# LED-Reorg-SMD.net
KiCad netlist of a schematic drawn in EAGLE
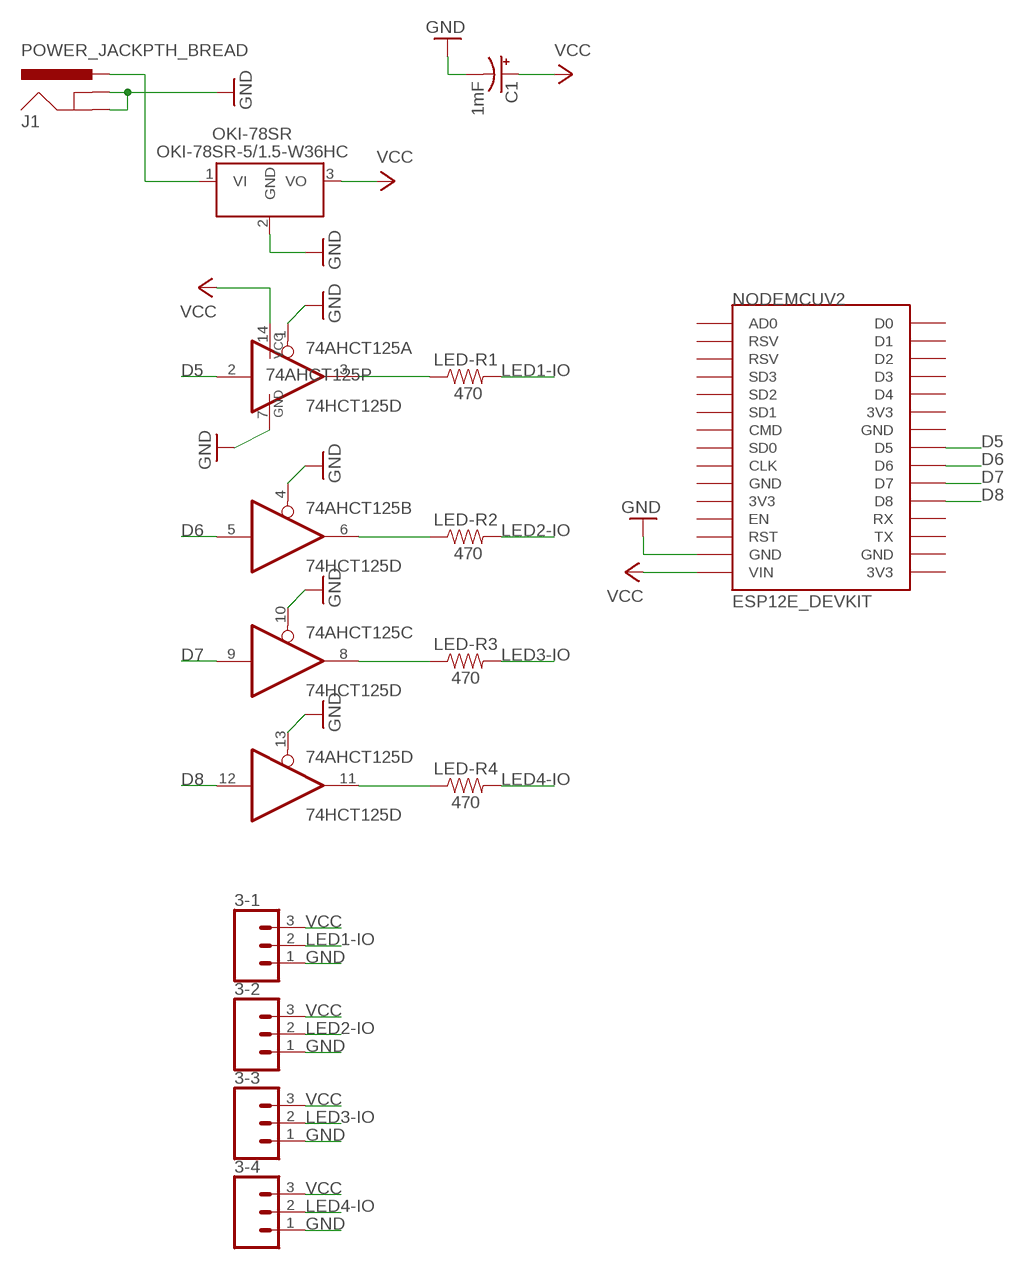
[diagram p0: schematic, sheet 1]

(export (version "E")
  (design (tool "Eeschema 10.0.6"))
  (components
    (comp (ref "3-1")
      (value "CONN_03SCREW")
      (footprint "eagle-import:SCREWTERMINAL-3.5MM-3")
      (libsource (lib "eagle-import") (part "CONN_03SCREW"))
    )
    (comp (ref "3-2")
      (value "CONN_03SCREW")
      (footprint "eagle-import:SCREWTERMINAL-3.5MM-3")
      (libsource (lib "eagle-import") (part "CONN_03SCREW"))
    )
    (comp (ref "3-3")
      (value "CONN_03SCREW")
      (footprint "eagle-import:SCREWTERMINAL-3.5MM-3")
      (libsource (lib "eagle-import") (part "CONN_03SCREW"))
    )
    (comp (ref "3-4")
      (value "CONN_03SCREW")
      (footprint "eagle-import:SCREWTERMINAL-3.5MM-3")
      (libsource (lib "eagle-import") (part "CONN_03SCREW"))
    )
    (comp (ref "74AHCT125")
      (value "74HCT125D")
      (footprint "eagle-import:SO14")
      (libsource (lib "eagle-import") (part "74125DHCT"))
    )
    (comp (ref "C1")
      (value "1mF")
      (footprint "eagle-import:CPOL-RADIAL-5MM-10MM")
      (libsource (lib "eagle-import") (part "1000UF-RADIAL-5MM-25V-20%"))
    )
    (comp (ref "J1")
      (value "POWER_JACKPTH_BREAD")
      (footprint "eagle-import:POWER_JACK_PTH_BREAD")
      (libsource (lib "eagle-import") (part "POWER_JACKPTH_BREAD"))
    )
    (comp (ref "LED-R1")
      (value "470")
      (footprint "eagle-import:1206")
      (libsource (lib "eagle-import") (part "RESISTOR1206"))
    )
    (comp (ref "LED-R2")
      (value "470")
      (footprint "eagle-import:1206")
      (libsource (lib "eagle-import") (part "RESISTOR1206"))
    )
    (comp (ref "LED-R3")
      (value "470")
      (footprint "eagle-import:1206")
      (libsource (lib "eagle-import") (part "RESISTOR1206"))
    )
    (comp (ref "LED-R4")
      (value "470")
      (footprint "eagle-import:1206")
      (libsource (lib "eagle-import") (part "RESISTOR1206"))
    )
    (comp (ref "NODEMCUV2")
      (value "ESP12E_DEVKIT")
      (footprint "eagle-import:ESP12E_DEVKIT")
      (libsource (lib "eagle-import") (part "ESP12E_DEVKIT"))
    )
    (comp (ref "OKI-78SR")
      (value "OKI-78SR-5/1.5-W36HC")
      (footprint "eagle-import:OKI-78SR_HORIZ")
      (libsource (lib "eagle-import") (part "OKI-78SR-/1.5-W36?CH5"))
    )
  )
  (nets
    (net (code "1") (name "/D5") (class "Default")
      (node (ref "74AHCT125") (pin "2") (pinfunction "I_2") (pintype "input"))
      (node (ref "NODEMCUV2") (pin "D5") (pinfunction "D5_D5") (pintype "bidirectional"))
    )
    (net (code "2") (name "/D6") (class "Default")
      (node (ref "74AHCT125") (pin "5") (pinfunction "I_5") (pintype "input"))
      (node (ref "NODEMCUV2") (pin "D6") (pinfunction "D6_D6") (pintype "bidirectional"))
    )
    (net (code "3") (name "/D7") (class "Default")
      (node (ref "74AHCT125") (pin "9") (pinfunction "I_9") (pintype "input"))
      (node (ref "NODEMCUV2") (pin "D7") (pinfunction "D7_D7") (pintype "bidirectional"))
    )
    (net (code "4") (name "/D8") (class "Default")
      (node (ref "74AHCT125") (pin "12") (pinfunction "I_12") (pintype "input"))
      (node (ref "NODEMCUV2") (pin "D8") (pinfunction "D8_D8") (pintype "bidirectional"))
    )
    (net (code "5") (name "/LED1-IO") (class "Default")
      (node (ref "3-1") (pin "2") (pinfunction "2_2") (pintype "passive"))
      (node (ref "LED-R1") (pin "2") (pinfunction "2_2") (pintype "passive"))
    )
    (net (code "6") (name "/LED2-IO") (class "Default")
      (node (ref "3-2") (pin "2") (pinfunction "2_2") (pintype "passive"))
      (node (ref "LED-R2") (pin "2") (pinfunction "2_2") (pintype "passive"))
    )
    (net (code "7") (name "/LED3-IO") (class "Default")
      (node (ref "3-3") (pin "2") (pinfunction "2_2") (pintype "passive"))
      (node (ref "LED-R3") (pin "2") (pinfunction "2_2") (pintype "passive"))
    )
    (net (code "8") (name "/LED4-IO") (class "Default")
      (node (ref "3-4") (pin "2") (pinfunction "2_2") (pintype "passive"))
      (node (ref "LED-R4") (pin "2") (pinfunction "2_2") (pintype "passive"))
    )
    (net (code "9") (name "GND") (class "Default")
      (node (ref "3-1") (pin "1") (pinfunction "1_1") (pintype "passive"))
      (node (ref "3-2") (pin "1") (pinfunction "1_1") (pintype "passive"))
      (node (ref "3-3") (pin "1") (pinfunction "1_1") (pintype "passive"))
      (node (ref "3-4") (pin "1") (pinfunction "1_1") (pintype "passive"))
      (node (ref "74AHCT125") (pin "1") (pinfunction "OE_1") (pintype "input"))
      (node (ref "74AHCT125") (pin "10") (pinfunction "OE_10") (pintype "input"))
      (node (ref "74AHCT125") (pin "13") (pinfunction "OE_13") (pintype "input"))
      (node (ref "74AHCT125") (pin "4") (pinfunction "OE_4") (pintype "input"))
      (node (ref "74AHCT125") (pin "7") (pinfunction "GND_7") (pintype "power_in"))
      (node (ref "C1") (pin "-") (pinfunction "-_-") (pintype "passive"))
      (node (ref "J1") (pin "GND") (pinfunction "GND_GND") (pintype "bidirectional"))
      (node (ref "J1") (pin "GNDBREAK") (pinfunction "GNDBREAK_GNDBREAK") (pintype "bidirectional"))
      (node (ref "NODEMCUV2") (pin "GND@1") (pinfunction "GND_GND@1") (pintype "bidirectional"))
      (node (ref "OKI-78SR") (pin "2") (pinfunction "GND_2") (pintype "bidirectional"))
    )
    (net (code "10") (name "Net-(74AHCT125A-O)") (class "Default")
      (node (ref "74AHCT125") (pin "3") (pinfunction "O_3") (pintype "tri_state"))
      (node (ref "LED-R1") (pin "1") (pinfunction "1_1") (pintype "passive"))
    )
    (net (code "11") (name "Net-(74AHCT125B-O)") (class "Default")
      (node (ref "74AHCT125") (pin "6") (pinfunction "O_6") (pintype "tri_state"))
      (node (ref "LED-R2") (pin "1") (pinfunction "1_1") (pintype "passive"))
    )
    (net (code "12") (name "Net-(74AHCT125C-O)") (class "Default")
      (node (ref "74AHCT125") (pin "8") (pinfunction "O_8") (pintype "tri_state"))
      (node (ref "LED-R3") (pin "1") (pinfunction "1_1") (pintype "passive"))
    )
    (net (code "13") (name "Net-(74AHCT125D-O)") (class "Default")
      (node (ref "74AHCT125") (pin "11") (pinfunction "O_11") (pintype "tri_state"))
      (node (ref "LED-R4") (pin "1") (pinfunction "1_1") (pintype "passive"))
    )
    (net (code "14") (name "Net-(OKI-78SR-VI)") (class "Default")
      (node (ref "J1") (pin "PWR") (pinfunction "PWR_PWR") (pintype "bidirectional"))
      (node (ref "OKI-78SR") (pin "1") (pinfunction "VI_1") (pintype "bidirectional"))
    )
    (net (code "15") (name "VCC") (class "Default")
      (node (ref "3-1") (pin "3") (pinfunction "3_3") (pintype "passive"))
      (node (ref "3-2") (pin "3") (pinfunction "3_3") (pintype "passive"))
      (node (ref "3-3") (pin "3") (pinfunction "3_3") (pintype "passive"))
      (node (ref "3-4") (pin "3") (pinfunction "3_3") (pintype "passive"))
      (node (ref "74AHCT125") (pin "14") (pinfunction "VCC_14") (pintype "power_in"))
      (node (ref "C1") (pin "+") (pinfunction "+_+") (pintype "passive"))
      (node (ref "NODEMCUV2") (pin "VIN") (pinfunction "VIN_VIN") (pintype "bidirectional"))
      (node (ref "OKI-78SR") (pin "3") (pinfunction "VO_3") (pintype "bidirectional"))
    )
    (net (code "16") (name "unconnected-(NODEMCUV2-3V3-Pad3V3@0)") (class "Default")
      (node (ref "NODEMCUV2") (pin "3V3@0") (pinfunction "3V3_3V3@0") (pintype "bidirectional"))
    )
    (net (code "17") (name "unconnected-(NODEMCUV2-3V3-Pad3V3@1)") (class "Default")
      (node (ref "NODEMCUV2") (pin "3V3@1") (pinfunction "3V3_3V3@1") (pintype "bidirectional"))
    )
    (net (code "18") (name "unconnected-(NODEMCUV2-3V3-Pad3V3@2)") (class "Default")
      (node (ref "NODEMCUV2") (pin "3V3@2") (pinfunction "3V3_3V3@2") (pintype "bidirectional"))
    )
    (net (code "19") (name "unconnected-(NODEMCUV2-GND-PadGND@0)") (class "Default")
      (node (ref "NODEMCUV2") (pin "GND@0") (pinfunction "GND_GND@0") (pintype "bidirectional"))
    )
    (net (code "20") (name "unconnected-(NODEMCUV2-GND-PadGND@2)") (class "Default")
      (node (ref "NODEMCUV2") (pin "GND@2") (pinfunction "GND_GND@2") (pintype "bidirectional"))
    )
    (net (code "21") (name "unconnected-(NODEMCUV2-GND-PadGND@3)") (class "Default")
      (node (ref "NODEMCUV2") (pin "GND@3") (pinfunction "GND_GND@3") (pintype "bidirectional"))
    )
    (net (code "22") (name "unconnected-(NODEMCUV2-PadAD0)") (class "Default")
      (node (ref "NODEMCUV2") (pin "AD0") (pinfunction "AD0_AD0") (pintype "bidirectional"))
    )
    (net (code "23") (name "unconnected-(NODEMCUV2-PadCLK)") (class "Default")
      (node (ref "NODEMCUV2") (pin "CLK") (pinfunction "CLK_CLK") (pintype "bidirectional"))
    )
    (net (code "24") (name "unconnected-(NODEMCUV2-PadCMD)") (class "Default")
      (node (ref "NODEMCUV2") (pin "CMD") (pinfunction "CMD_CMD") (pintype "bidirectional"))
    )
    (net (code "25") (name "unconnected-(NODEMCUV2-PadD0)") (class "Default")
      (node (ref "NODEMCUV2") (pin "D0") (pinfunction "D0_D0") (pintype "bidirectional"))
    )
    (net (code "26") (name "unconnected-(NODEMCUV2-PadD1)") (class "Default")
      (node (ref "NODEMCUV2") (pin "D1") (pinfunction "D1_D1") (pintype "bidirectional"))
    )
    (net (code "27") (name "unconnected-(NODEMCUV2-PadD2)") (class "Default")
      (node (ref "NODEMCUV2") (pin "D2") (pinfunction "D2_D2") (pintype "bidirectional"))
    )
    (net (code "28") (name "unconnected-(NODEMCUV2-PadD3)") (class "Default")
      (node (ref "NODEMCUV2") (pin "D3") (pinfunction "D3_D3") (pintype "bidirectional"))
    )
    (net (code "29") (name "unconnected-(NODEMCUV2-PadD4)") (class "Default")
      (node (ref "NODEMCUV2") (pin "D4") (pinfunction "D4_D4") (pintype "bidirectional"))
    )
    (net (code "30") (name "unconnected-(NODEMCUV2-PadEN)") (class "Default")
      (node (ref "NODEMCUV2") (pin "EN") (pinfunction "EN_EN") (pintype "bidirectional"))
    )
    (net (code "31") (name "unconnected-(NODEMCUV2-PadRST)") (class "Default")
      (node (ref "NODEMCUV2") (pin "RST") (pinfunction "RST_RST") (pintype "bidirectional"))
    )
    (net (code "32") (name "unconnected-(NODEMCUV2-PadRX)") (class "Default")
      (node (ref "NODEMCUV2") (pin "RX") (pinfunction "RX_RX") (pintype "bidirectional"))
    )
    (net (code "33") (name "unconnected-(NODEMCUV2-PadSD0)") (class "Default")
      (node (ref "NODEMCUV2") (pin "SD0") (pinfunction "SD0_SD0") (pintype "bidirectional"))
    )
    (net (code "34") (name "unconnected-(NODEMCUV2-PadSD1)") (class "Default")
      (node (ref "NODEMCUV2") (pin "SD1") (pinfunction "SD1_SD1") (pintype "bidirectional"))
    )
    (net (code "35") (name "unconnected-(NODEMCUV2-PadSD2)") (class "Default")
      (node (ref "NODEMCUV2") (pin "SD2") (pinfunction "SD2_SD2") (pintype "bidirectional"))
    )
    (net (code "36") (name "unconnected-(NODEMCUV2-PadSD3)") (class "Default")
      (node (ref "NODEMCUV2") (pin "SD3") (pinfunction "SD3_SD3") (pintype "bidirectional"))
    )
    (net (code "37") (name "unconnected-(NODEMCUV2-PadTX)") (class "Default")
      (node (ref "NODEMCUV2") (pin "TX") (pinfunction "TX_TX") (pintype "bidirectional"))
    )
    (net (code "38") (name "unconnected-(NODEMCUV2-RSV-PadRSV@0)") (class "Default")
      (node (ref "NODEMCUV2") (pin "RSV@0") (pinfunction "RSV_RSV@0") (pintype "bidirectional"))
    )
    (net (code "39") (name "unconnected-(NODEMCUV2-RSV-PadRSV@1)") (class "Default")
      (node (ref "NODEMCUV2") (pin "RSV@1") (pinfunction "RSV_RSV@1") (pintype "bidirectional"))
    )
  )
)
